# pump.net
KiCad netlist of a schematic drawn in Altium Designer
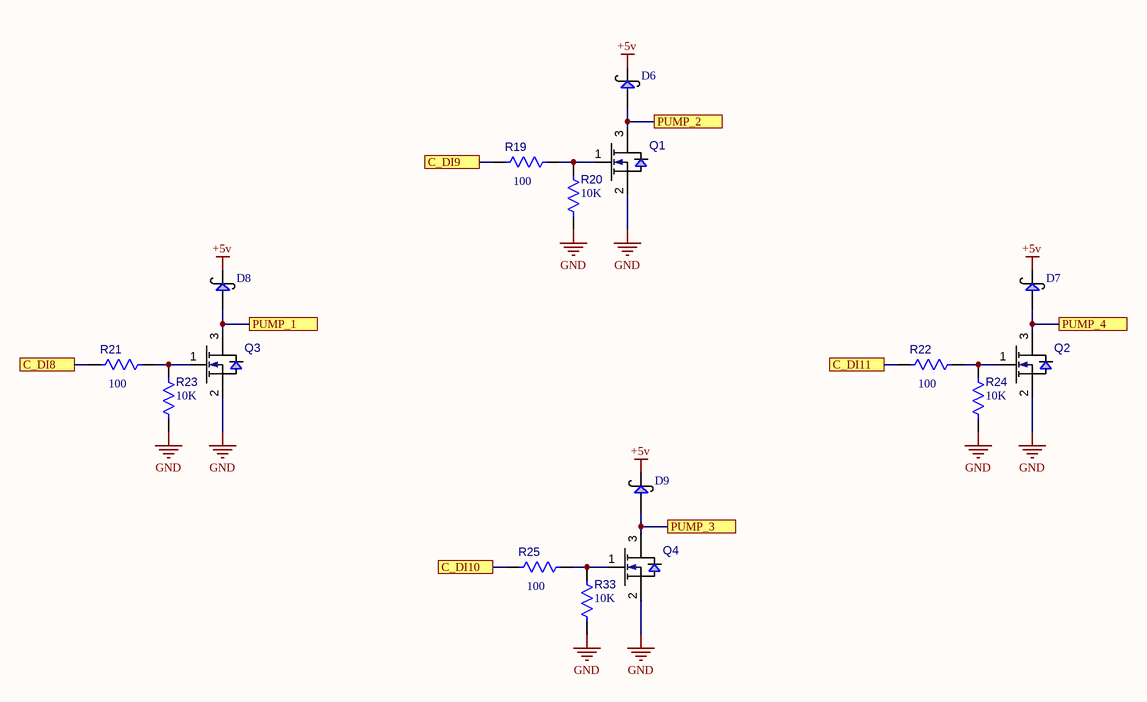
[diagram p0: pump.SchDoc]

(export (version "E")
  (design (tool "Eeschema 10.0.6"))
  (components
    (comp (ref "D6")
      (value "~")
      (footprint "SOD123")
      (description "SOD123")
      (libsource (lib "mylib") (part "MBRX160"))
    )
    (comp (ref "D7")
      (value "~")
      (footprint "SOD123")
      (description "SOD123")
      (libsource (lib "mylib") (part "MBRX160"))
    )
    (comp (ref "D8")
      (value "~")
      (footprint "SOD123")
      (description "SOD123")
      (libsource (lib "mylib") (part "MBRX160"))
    )
    (comp (ref "D9")
      (value "~")
      (footprint "SOD123")
      (description "SOD123")
      (libsource (lib "mylib") (part "MBRX160"))
    )
    (comp (ref "Q1")
      (value "BSS138")
      (footprint "SOT23_N_123")
      (description "N-Channel MOSFET")
      (fields (field (name "MANUFACTURER") "Fairchild"))
      (libsource (lib "mylib") (part "BSS138"))
    )
    (comp (ref "Q2")
      (value "BSS138")
      (footprint "SOT23_N_123")
      (description "N-Channel MOSFET")
      (fields (field (name "MANUFACTURER") "Fairchild"))
      (libsource (lib "mylib") (part "BSS138"))
    )
    (comp (ref "Q3")
      (value "BSS138")
      (footprint "SOT23_N_123")
      (description "N-Channel MOSFET")
      (fields (field (name "MANUFACTURER") "Fairchild"))
      (libsource (lib "mylib") (part "BSS138"))
    )
    (comp (ref "Q4")
      (value "BSS138")
      (footprint "SOT23_N_123")
      (description "N-Channel MOSFET")
      (fields (field (name "MANUFACTURER") "Fairchild"))
      (libsource (lib "mylib") (part "BSS138"))
    )
    (comp (ref "R19")
      (value "100")
      (footprint "0805")
      (description "Resistor")
      (fields (field (name "TOLERANCE") "1%"))
      (libsource (lib "mylib_franco") (part "Res"))
    )
    (comp (ref "R20")
      (value "10K")
      (footprint "0805")
      (description "Resistor")
      (fields (field (name "TOLERANCE") "1%"))
      (libsource (lib "mylib") (part "Res"))
    )
    (comp (ref "R21")
      (value "100")
      (footprint "0805")
      (description "Resistor")
      (fields (field (name "TOLERANCE") "1%"))
      (libsource (lib "mylib_franco") (part "Res"))
    )
    (comp (ref "R22")
      (value "100")
      (footprint "0805")
      (description "Resistor")
      (fields (field (name "TOLERANCE") "1%"))
      (libsource (lib "mylib_franco") (part "Res"))
    )
    (comp (ref "R23")
      (value "10K")
      (footprint "0805")
      (description "Resistor")
      (fields (field (name "TOLERANCE") "1%"))
      (libsource (lib "mylib") (part "Res"))
    )
    (comp (ref "R24")
      (value "10K")
      (footprint "0805")
      (description "Resistor")
      (fields (field (name "TOLERANCE") "1%"))
      (libsource (lib "mylib") (part "Res"))
    )
    (comp (ref "R25")
      (value "100")
      (footprint "0805")
      (description "Resistor")
      (fields (field (name "TOLERANCE") "1%"))
      (libsource (lib "mylib_franco") (part "Res"))
    )
    (comp (ref "R33")
      (value "10K")
      (footprint "0805")
      (description "Resistor")
      (fields (field (name "TOLERANCE") "1%"))
      (libsource (lib "mylib") (part "Res"))
    )
  )
  (nets
    (net (code "1") (name "+5v") (class "Default")
      (node (ref "D6") (pin "2") (pinfunction "2_2") (pintype "passive"))
      (node (ref "D7") (pin "2") (pinfunction "2_2") (pintype "passive"))
      (node (ref "D8") (pin "2") (pinfunction "2_2") (pintype "passive"))
      (node (ref "D9") (pin "2") (pinfunction "2_2") (pintype "passive"))
    )
    (net (code "2") (name "/C_DI8") (class "Default")
      (node (ref "R21") (pin "1") (pinfunction "1_1") (pintype "passive"))
    )
    (net (code "3") (name "/C_DI9") (class "Default")
      (node (ref "R19") (pin "1") (pinfunction "1_1") (pintype "passive"))
    )
    (net (code "4") (name "/C_DI10") (class "Default")
      (node (ref "R25") (pin "1") (pinfunction "1_1") (pintype "passive"))
    )
    (net (code "5") (name "/C_DI11") (class "Default")
      (node (ref "R22") (pin "1") (pinfunction "1_1") (pintype "passive"))
    )
    (net (code "6") (name "/PUMP_1") (class "Default")
      (node (ref "D8") (pin "1") (pinfunction "1_1") (pintype "passive"))
      (node (ref "Q3") (pin "3") (pinfunction "3_3") (pintype "passive"))
    )
    (net (code "7") (name "/PUMP_2") (class "Default")
      (node (ref "D6") (pin "1") (pinfunction "1_1") (pintype "passive"))
      (node (ref "Q1") (pin "3") (pinfunction "3_3") (pintype "passive"))
    )
    (net (code "8") (name "/PUMP_3") (class "Default")
      (node (ref "D9") (pin "1") (pinfunction "1_1") (pintype "passive"))
      (node (ref "Q4") (pin "3") (pinfunction "3_3") (pintype "passive"))
    )
    (net (code "9") (name "/PUMP_4") (class "Default")
      (node (ref "D7") (pin "1") (pinfunction "1_1") (pintype "passive"))
      (node (ref "Q2") (pin "3") (pinfunction "3_3") (pintype "passive"))
    )
    (net (code "10") (name "GND") (class "Default")
      (node (ref "Q1") (pin "2") (pinfunction "2_2") (pintype "passive"))
      (node (ref "Q2") (pin "2") (pinfunction "2_2") (pintype "passive"))
      (node (ref "Q3") (pin "2") (pinfunction "2_2") (pintype "passive"))
      (node (ref "Q4") (pin "2") (pinfunction "2_2") (pintype "passive"))
      (node (ref "R20") (pin "1") (pinfunction "1_1") (pintype "passive"))
      (node (ref "R23") (pin "1") (pinfunction "1_1") (pintype "passive"))
      (node (ref "R24") (pin "1") (pinfunction "1_1") (pintype "passive"))
      (node (ref "R33") (pin "1") (pinfunction "1_1") (pintype "passive"))
    )
    (net (code "11") (name "Net-(Q1-Pad1)") (class "Default")
      (node (ref "Q1") (pin "1") (pinfunction "1_1") (pintype "passive"))
      (node (ref "R19") (pin "2") (pinfunction "2_2") (pintype "passive"))
      (node (ref "R20") (pin "2") (pinfunction "2_2") (pintype "passive"))
    )
    (net (code "12") (name "Net-(Q2-Pad1)") (class "Default")
      (node (ref "Q2") (pin "1") (pinfunction "1_1") (pintype "passive"))
      (node (ref "R22") (pin "2") (pinfunction "2_2") (pintype "passive"))
      (node (ref "R24") (pin "2") (pinfunction "2_2") (pintype "passive"))
    )
    (net (code "13") (name "Net-(Q3-Pad1)") (class "Default")
      (node (ref "Q3") (pin "1") (pinfunction "1_1") (pintype "passive"))
      (node (ref "R21") (pin "2") (pinfunction "2_2") (pintype "passive"))
      (node (ref "R23") (pin "2") (pinfunction "2_2") (pintype "passive"))
    )
    (net (code "14") (name "Net-(Q4-Pad1)") (class "Default")
      (node (ref "Q4") (pin "1") (pinfunction "1_1") (pintype "passive"))
      (node (ref "R25") (pin "2") (pinfunction "2_2") (pintype "passive"))
      (node (ref "R33") (pin "2") (pinfunction "2_2") (pintype "passive"))
    )
  )
)
